# babymidiproto2_shield.net
KiCad netlist of a schematic drawn in EAGLE
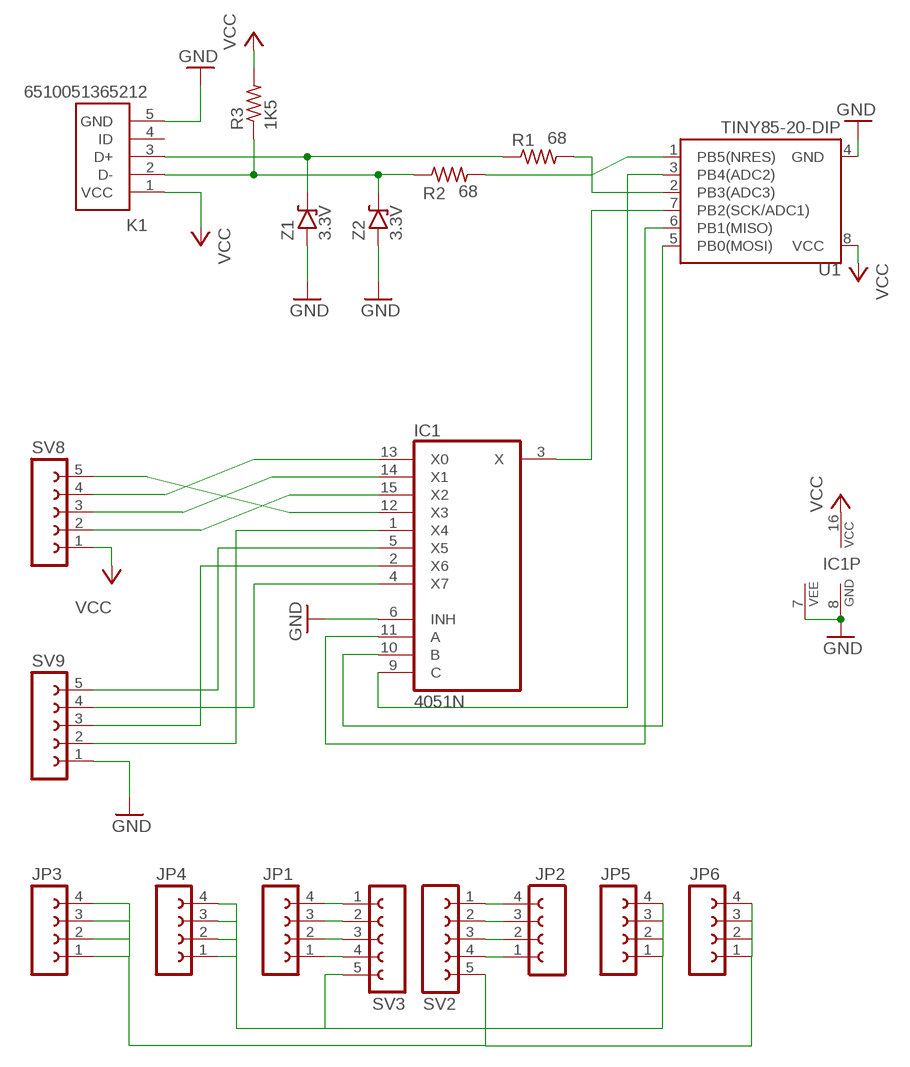
[diagram p0: schematic, sheet 1]

(export (version "E")
  (design (tool "Eeschema 10.0.6"))
  (components
    (comp (ref "IC1")
      (value "4051N")
      (footprint "eagle-import:DIL16")
      (libsource (lib "eagle-import") (part "4051N"))
    )
    (comp (ref "JP1")
      (value "FE04-1SQBIG")
      (footprint "eagle-import:FE04-1-SQUARE-BIG")
      (libsource (lib "eagle-import") (part "FE04-1SQBIG"))
    )
    (comp (ref "JP2")
      (value "FE04-1SQBIG")
      (footprint "eagle-import:FE04-1-SQUARE-BIG")
      (libsource (lib "eagle-import") (part "FE04-1SQBIG"))
    )
    (comp (ref "JP3")
      (value "FE04-1SQBIG")
      (footprint "eagle-import:FE04-1-SQUARE-BIG")
      (libsource (lib "eagle-import") (part "FE04-1SQBIG"))
    )
    (comp (ref "JP4")
      (value "FE04-1SQBIG")
      (footprint "eagle-import:FE04-1-SQUARE-BIG")
      (libsource (lib "eagle-import") (part "FE04-1SQBIG"))
    )
    (comp (ref "JP5")
      (value "FE04-1SQBIG")
      (footprint "eagle-import:FE04-1-SQUARE-BIG")
      (libsource (lib "eagle-import") (part "FE04-1SQBIG"))
    )
    (comp (ref "JP6")
      (value "FE04-1SQBIG")
      (footprint "eagle-import:FE04-1-SQUARE-BIG")
      (libsource (lib "eagle-import") (part "FE04-1SQBIG"))
    )
    (comp (ref "K1")
      (value "6510051365212")
      (footprint "eagle-import:MINIUSB_DIP")
      (libsource (lib "eagle-import") (part "6510051365212"))
    )
    (comp (ref "R1")
      (value "68")
      (footprint "eagle-import:0703")
      (libsource (lib "eagle-import") (part "7MM"))
    )
    (comp (ref "R2")
      (value "68")
      (footprint "eagle-import:0703")
      (libsource (lib "eagle-import") (part "7MM"))
    )
    (comp (ref "R3")
      (value "1K5")
      (footprint "eagle-import:0703")
      (libsource (lib "eagle-import") (part "7MM"))
    )
    (comp (ref "SV2")
      (value "FE05-1SQBIGGER")
      (footprint "eagle-import:FE05-1-SQUARE-BIGGER")
      (libsource (lib "eagle-import") (part "FE05-1SQBIGGER"))
    )
    (comp (ref "SV3")
      (value "FE05-1SQBIGGER")
      (footprint "eagle-import:FE05-1-SQUARE-BIGGER")
      (libsource (lib "eagle-import") (part "FE05-1SQBIGGER"))
    )
    (comp (ref "SV8")
      (value "FE05-1SQBIG")
      (footprint "eagle-import:FE05-1-SQUARE-BIG")
      (libsource (lib "eagle-import") (part "FE05-1SQBIG"))
    )
    (comp (ref "SV9")
      (value "FE05-1SQBIG")
      (footprint "eagle-import:FE05-1-SQUARE-BIG")
      (libsource (lib "eagle-import") (part "FE05-1SQBIG"))
    )
    (comp (ref "U1")
      (value "TINY85-20-DIP")
      (footprint "eagle-import:DIP08")
      (libsource (lib "eagle-import") (part "ATTINY45TINY85-20-DIP"))
    )
    (comp (ref "Z1")
      (value "3.3V")
      (footprint "eagle-import:DO41-2")
      (libsource (lib "eagle-import") (part "1N47XX2"))
    )
    (comp (ref "Z2")
      (value "3.3V")
      (footprint "eagle-import:DO41-2")
      (libsource (lib "eagle-import") (part "1N47XX2"))
    )
  )
  (nets
    (net (code "1") (name "GND") (class "Default")
      (node (ref "IC1") (pin "6") (pinfunction "INH_6") (pintype "input"))
      (node (ref "IC1") (pin "7") (pinfunction "VEE_7") (pintype "power_in"))
      (node (ref "IC1") (pin "8") (pinfunction "GND_8") (pintype "power_in"))
      (node (ref "K1") (pin "5") (pinfunction "GND_5") (pintype "passive"))
      (node (ref "SV9") (pin "1") (pinfunction "1_1") (pintype "passive"))
      (node (ref "U1") (pin "4") (pinfunction "GND_4") (pintype "bidirectional"))
      (node (ref "Z1") (pin "A") (pinfunction "A_A") (pintype "passive"))
      (node (ref "Z2") (pin "A") (pinfunction "A_A") (pintype "passive"))
    )
    (net (code "2") (name "Net-(IC1A-A)") (class "Default")
      (node (ref "IC1") (pin "11") (pinfunction "A_11") (pintype "input"))
      (node (ref "U1") (pin "6") (pinfunction "PB1(MISO)_6") (pintype "bidirectional"))
    )
    (net (code "3") (name "Net-(IC1A-B)") (class "Default")
      (node (ref "IC1") (pin "10") (pinfunction "B_10") (pintype "input"))
      (node (ref "U1") (pin "5") (pinfunction "PB0(MOSI)_5") (pintype "bidirectional"))
    )
    (net (code "4") (name "Net-(IC1A-C)") (class "Default")
      (node (ref "IC1") (pin "9") (pinfunction "C_9") (pintype "input"))
      (node (ref "U1") (pin "3") (pinfunction "PB4(ADC2)_3") (pintype "bidirectional"))
    )
    (net (code "5") (name "Net-(IC1A-X)") (class "Default")
      (node (ref "IC1") (pin "3") (pinfunction "X_3") (pintype "bidirectional"))
      (node (ref "U1") (pin "7") (pinfunction "PB2(SCK/ADC1)_7") (pintype "bidirectional"))
    )
    (net (code "6") (name "Net-(IC1A-X0)") (class "Default")
      (node (ref "IC1") (pin "13") (pinfunction "X0_13") (pintype "bidirectional"))
      (node (ref "SV8") (pin "4") (pinfunction "4_4") (pintype "passive"))
    )
    (net (code "7") (name "Net-(IC1A-X1)") (class "Default")
      (node (ref "IC1") (pin "14") (pinfunction "X1_14") (pintype "bidirectional"))
      (node (ref "SV8") (pin "3") (pinfunction "3_3") (pintype "passive"))
    )
    (net (code "8") (name "Net-(IC1A-X2)") (class "Default")
      (node (ref "IC1") (pin "15") (pinfunction "X2_15") (pintype "bidirectional"))
      (node (ref "SV8") (pin "2") (pinfunction "2_2") (pintype "passive"))
    )
    (net (code "9") (name "Net-(IC1A-X3)") (class "Default")
      (node (ref "IC1") (pin "12") (pinfunction "X3_12") (pintype "bidirectional"))
      (node (ref "SV8") (pin "5") (pinfunction "5_5") (pintype "passive"))
    )
    (net (code "10") (name "Net-(IC1A-X4)") (class "Default")
      (node (ref "IC1") (pin "1") (pinfunction "X4_1") (pintype "bidirectional"))
      (node (ref "SV9") (pin "2") (pinfunction "2_2") (pintype "passive"))
    )
    (net (code "11") (name "Net-(IC1A-X5)") (class "Default")
      (node (ref "IC1") (pin "5") (pinfunction "X5_5") (pintype "bidirectional"))
      (node (ref "SV9") (pin "5") (pinfunction "5_5") (pintype "passive"))
    )
    (net (code "12") (name "Net-(IC1A-X6)") (class "Default")
      (node (ref "IC1") (pin "2") (pinfunction "X6_2") (pintype "bidirectional"))
      (node (ref "SV9") (pin "3") (pinfunction "3_3") (pintype "passive"))
    )
    (net (code "13") (name "Net-(IC1A-X7)") (class "Default")
      (node (ref "IC1") (pin "4") (pinfunction "X7_4") (pintype "bidirectional"))
      (node (ref "SV9") (pin "4") (pinfunction "4_4") (pintype "passive"))
    )
    (net (code "14") (name "Net-(JP1-Pad1)") (class "Default")
      (node (ref "JP1") (pin "1") (pinfunction "1_1") (pintype "passive"))
      (node (ref "SV3") (pin "4") (pinfunction "4_4") (pintype "passive"))
    )
    (net (code "15") (name "Net-(JP1-Pad2)") (class "Default")
      (node (ref "JP1") (pin "2") (pinfunction "2_2") (pintype "passive"))
      (node (ref "SV3") (pin "3") (pinfunction "3_3") (pintype "passive"))
    )
    (net (code "16") (name "Net-(JP1-Pad3)") (class "Default")
      (node (ref "JP1") (pin "3") (pinfunction "3_3") (pintype "passive"))
      (node (ref "SV3") (pin "2") (pinfunction "2_2") (pintype "passive"))
    )
    (net (code "17") (name "Net-(JP1-Pad4)") (class "Default")
      (node (ref "JP1") (pin "4") (pinfunction "4_4") (pintype "passive"))
      (node (ref "SV3") (pin "1") (pinfunction "1_1") (pintype "passive"))
    )
    (net (code "18") (name "Net-(JP2-Pad1)") (class "Default")
      (node (ref "JP2") (pin "1") (pinfunction "1_1") (pintype "passive"))
      (node (ref "SV2") (pin "4") (pinfunction "4_4") (pintype "passive"))
    )
    (net (code "19") (name "Net-(JP2-Pad2)") (class "Default")
      (node (ref "JP2") (pin "2") (pinfunction "2_2") (pintype "passive"))
      (node (ref "SV2") (pin "3") (pinfunction "3_3") (pintype "passive"))
    )
    (net (code "20") (name "Net-(JP2-Pad3)") (class "Default")
      (node (ref "JP2") (pin "3") (pinfunction "3_3") (pintype "passive"))
      (node (ref "SV2") (pin "2") (pinfunction "2_2") (pintype "passive"))
    )
    (net (code "21") (name "Net-(JP2-Pad4)") (class "Default")
      (node (ref "JP2") (pin "4") (pinfunction "4_4") (pintype "passive"))
      (node (ref "SV2") (pin "1") (pinfunction "1_1") (pintype "passive"))
    )
    (net (code "22") (name "Net-(JP3-Pad1)") (class "Default")
      (node (ref "JP3") (pin "1") (pinfunction "1_1") (pintype "passive"))
      (node (ref "JP3") (pin "2") (pinfunction "2_2") (pintype "passive"))
      (node (ref "JP3") (pin "3") (pinfunction "3_3") (pintype "passive"))
      (node (ref "JP3") (pin "4") (pinfunction "4_4") (pintype "passive"))
      (node (ref "JP6") (pin "1") (pinfunction "1_1") (pintype "passive"))
      (node (ref "JP6") (pin "2") (pinfunction "2_2") (pintype "passive"))
      (node (ref "JP6") (pin "3") (pinfunction "3_3") (pintype "passive"))
      (node (ref "JP6") (pin "4") (pinfunction "4_4") (pintype "passive"))
      (node (ref "SV2") (pin "5") (pinfunction "5_5") (pintype "passive"))
    )
    (net (code "23") (name "Net-(JP4-Pad1)") (class "Default")
      (node (ref "JP4") (pin "1") (pinfunction "1_1") (pintype "passive"))
      (node (ref "JP4") (pin "2") (pinfunction "2_2") (pintype "passive"))
      (node (ref "JP4") (pin "3") (pinfunction "3_3") (pintype "passive"))
      (node (ref "JP4") (pin "4") (pinfunction "4_4") (pintype "passive"))
      (node (ref "JP5") (pin "1") (pinfunction "1_1") (pintype "passive"))
      (node (ref "JP5") (pin "2") (pinfunction "2_2") (pintype "passive"))
      (node (ref "JP5") (pin "3") (pinfunction "3_3") (pintype "passive"))
      (node (ref "JP5") (pin "4") (pinfunction "4_4") (pintype "passive"))
      (node (ref "SV3") (pin "5") (pinfunction "5_5") (pintype "passive"))
    )
    (net (code "24") (name "Net-(K1-D+)") (class "Default")
      (node (ref "K1") (pin "3") (pinfunction "D+_3") (pintype "passive"))
      (node (ref "R1") (pin "1") (pinfunction "1_1") (pintype "passive"))
      (node (ref "Z1") (pin "C") (pinfunction "C_C") (pintype "passive"))
    )
    (net (code "25") (name "Net-(K1-D-)") (class "Default")
      (node (ref "K1") (pin "2") (pinfunction "D-_2") (pintype "passive"))
      (node (ref "R2") (pin "1") (pinfunction "1_1") (pintype "passive"))
      (node (ref "R3") (pin "1") (pinfunction "1_1") (pintype "passive"))
      (node (ref "Z2") (pin "C") (pinfunction "C_C") (pintype "passive"))
    )
    (net (code "26") (name "Net-(U1-PB3(ADC3))") (class "Default")
      (node (ref "R1") (pin "2") (pinfunction "2_2") (pintype "passive"))
      (node (ref "U1") (pin "2") (pinfunction "PB3(ADC3)_2") (pintype "bidirectional"))
    )
    (net (code "27") (name "Net-(U1-PB5(NRES))") (class "Default")
      (node (ref "R2") (pin "2") (pinfunction "2_2") (pintype "passive"))
      (node (ref "U1") (pin "1") (pinfunction "PB5(NRES)_1") (pintype "bidirectional"))
    )
    (net (code "28") (name "VCC") (class "Default")
      (node (ref "IC1") (pin "16") (pinfunction "VCC_16") (pintype "power_in"))
      (node (ref "K1") (pin "1") (pinfunction "VCC_1") (pintype "passive"))
      (node (ref "R3") (pin "2") (pinfunction "2_2") (pintype "passive"))
      (node (ref "SV8") (pin "1") (pinfunction "1_1") (pintype "passive"))
      (node (ref "U1") (pin "8") (pinfunction "VCC_8") (pintype "bidirectional"))
    )
    (net (code "29") (name "unconnected-(K1-ID-Pad4)") (class "Default")
      (node (ref "K1") (pin "4") (pinfunction "ID_4") (pintype "passive"))
    )
  )
)
